# Functional_Schematic.net
KiCad netlist of a schematic drawn in EAGLE
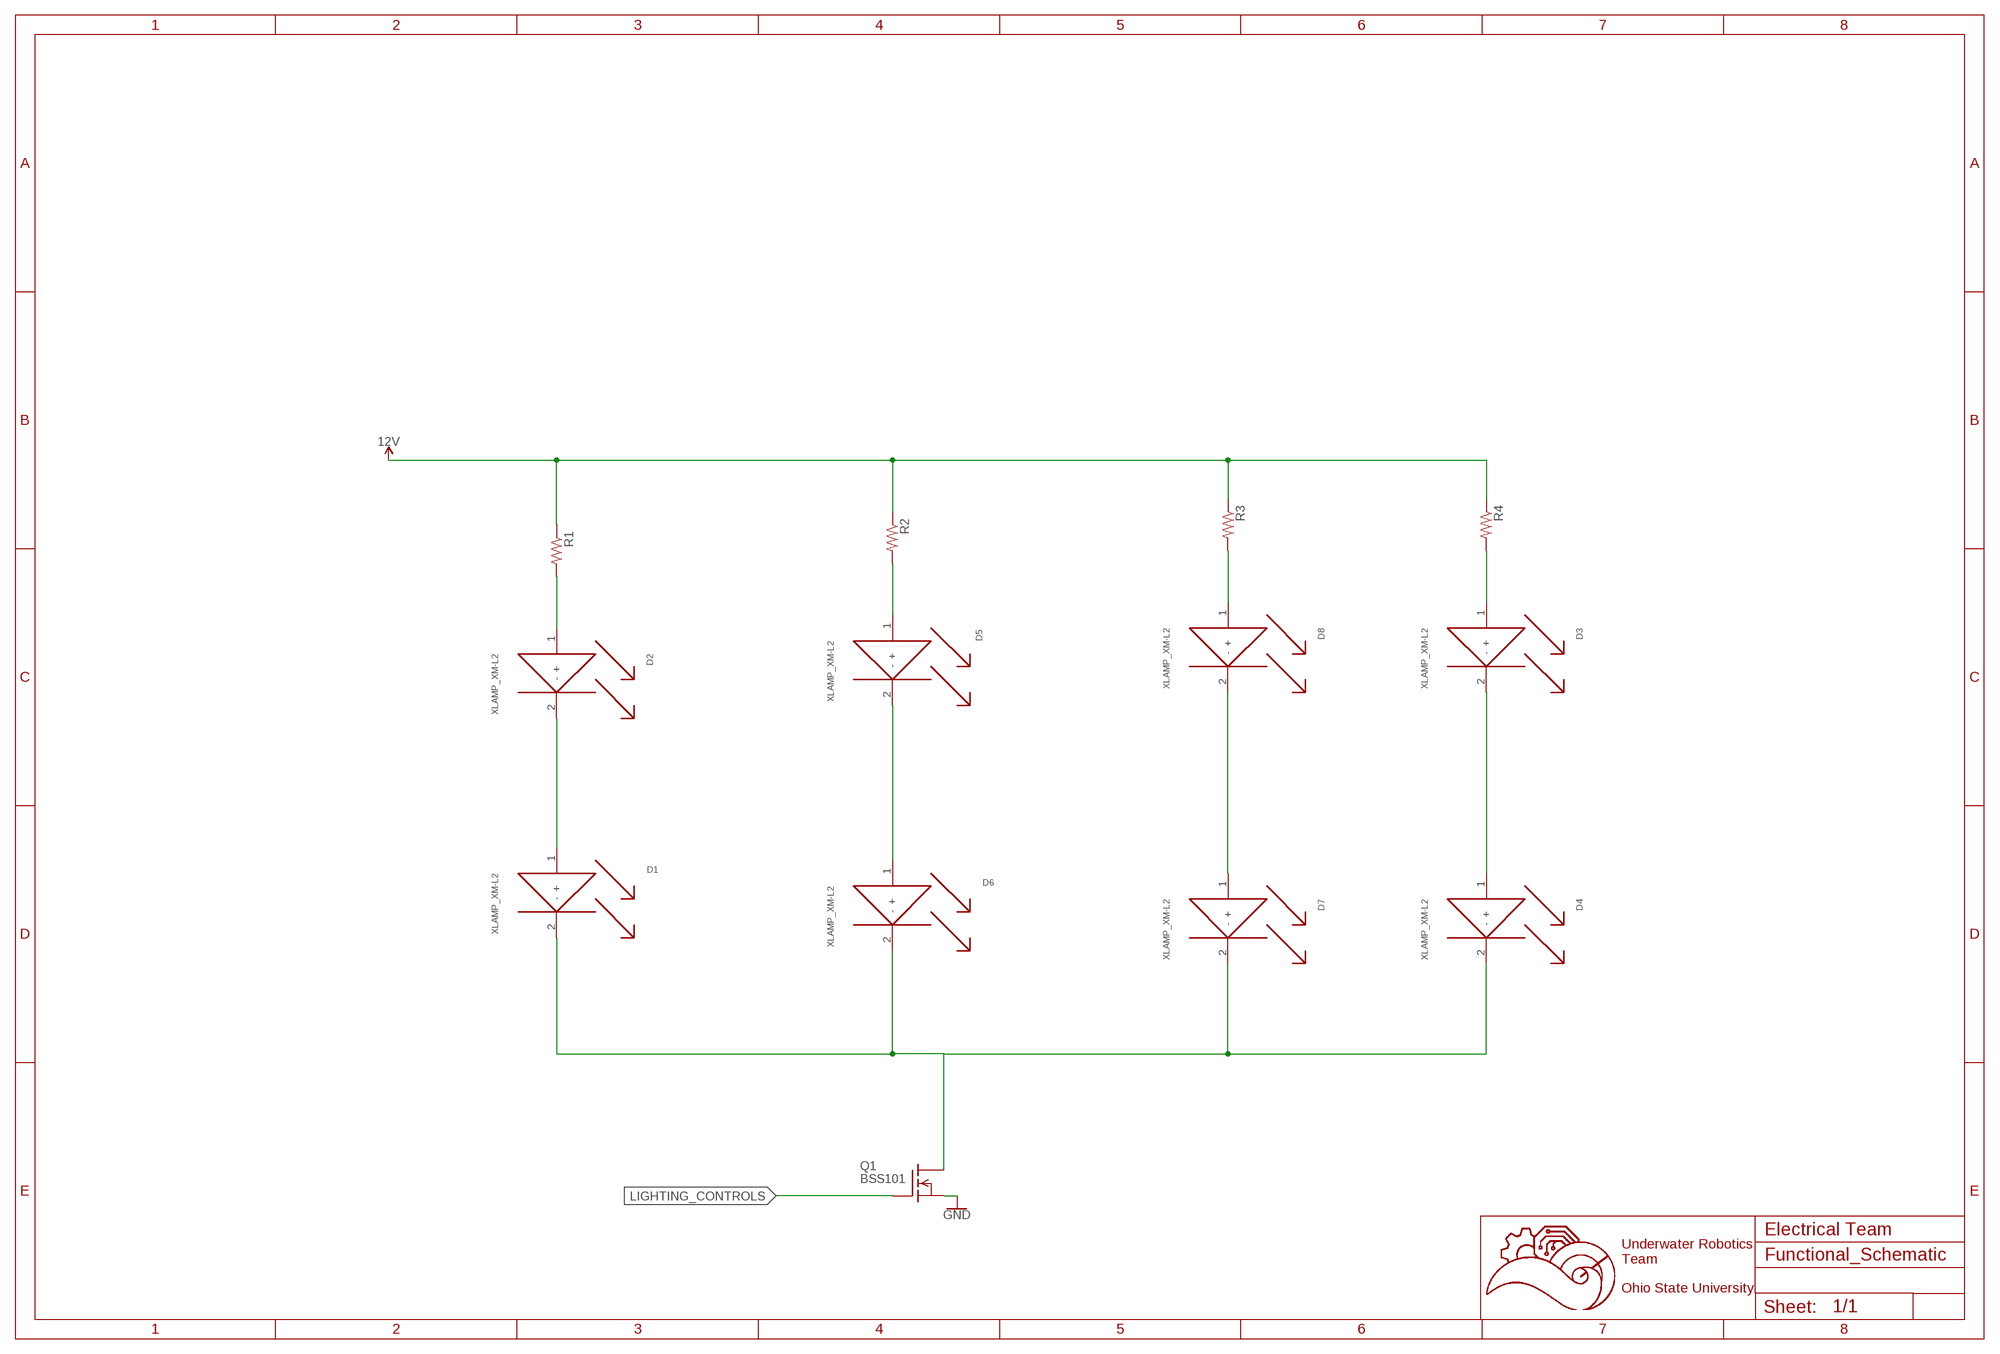
[diagram p0: schematic, sheet 1]

(export (version "E")
  (design (tool "Eeschema 10.0.6"))
  (components
    (comp (ref "D1")
      (value "XLAMP_XM-L2")
      (footprint "eagle-import:XLAMP_XM-L2")
      (libsource (lib "eagle-import") (part "XLAMP_XM-L2"))
    )
    (comp (ref "D2")
      (value "XLAMP_XM-L2")
      (footprint "eagle-import:XLAMP_XM-L2")
      (libsource (lib "eagle-import") (part "XLAMP_XM-L2"))
    )
    (comp (ref "D3")
      (value "XLAMP_XM-L2")
      (footprint "eagle-import:XLAMP_XM-L2")
      (libsource (lib "eagle-import") (part "XLAMP_XM-L2"))
    )
    (comp (ref "D4")
      (value "XLAMP_XM-L2")
      (footprint "eagle-import:XLAMP_XM-L2")
      (libsource (lib "eagle-import") (part "XLAMP_XM-L2"))
    )
    (comp (ref "D5")
      (value "XLAMP_XM-L2")
      (footprint "eagle-import:XLAMP_XM-L2")
      (libsource (lib "eagle-import") (part "XLAMP_XM-L2"))
    )
    (comp (ref "D6")
      (value "XLAMP_XM-L2")
      (footprint "eagle-import:XLAMP_XM-L2")
      (libsource (lib "eagle-import") (part "XLAMP_XM-L2"))
    )
    (comp (ref "D7")
      (value "XLAMP_XM-L2")
      (footprint "eagle-import:XLAMP_XM-L2")
      (libsource (lib "eagle-import") (part "XLAMP_XM-L2"))
    )
    (comp (ref "D8")
      (value "XLAMP_XM-L2")
      (footprint "eagle-import:XLAMP_XM-L2")
      (libsource (lib "eagle-import") (part "XLAMP_XM-L2"))
    )
    (comp (ref "Q1")
      (value "BSS101")
      (footprint "eagle-import:TO92")
      (libsource (lib "eagle-import") (part "BSS101"))
    )
    (comp (ref "R1")
      (value "R-US_R0603")
      (footprint "eagle-import:R0603")
      (libsource (lib "eagle-import") (part "R-US_R0603"))
    )
    (comp (ref "R2")
      (value "R-US_R0603")
      (footprint "eagle-import:R0603")
      (libsource (lib "eagle-import") (part "R-US_R0603"))
    )
    (comp (ref "R3")
      (value "R-US_R0603")
      (footprint "eagle-import:R0603")
      (libsource (lib "eagle-import") (part "R-US_R0603"))
    )
    (comp (ref "R4")
      (value "R-US_R0603")
      (footprint "eagle-import:R0603")
      (libsource (lib "eagle-import") (part "R-US_R0603"))
    )
  )
  (nets
    (net (code "1") (name "12V") (class "Default")
      (node (ref "R1") (pin "1") (pinfunction "1_1") (pintype "passive"))
      (node (ref "R2") (pin "1") (pinfunction "1_1") (pintype "passive"))
      (node (ref "R3") (pin "1") (pinfunction "1_1") (pintype "passive"))
      (node (ref "R4") (pin "1") (pinfunction "1_1") (pintype "passive"))
    )
    (net (code "2") (name "GND") (class "Default")
      (node (ref "Q1") (pin "1") (pinfunction "S_1") (pintype "passive"))
    )
    (net (code "3") (name "LIGHTING_CONTROLS") (class "Default")
      (node (ref "Q1") (pin "2") (pinfunction "G_2") (pintype "passive"))
    )
    (net (code "4") (name "Net-(D1-+)") (class "Default")
      (node (ref "D1") (pin "1") (pinfunction "+_1") (pintype "bidirectional"))
      (node (ref "D2") (pin "2") (pinfunction "-_2") (pintype "bidirectional"))
    )
    (net (code "5") (name "Net-(D1--)") (class "Default")
      (node (ref "D1") (pin "2") (pinfunction "-_2") (pintype "bidirectional"))
      (node (ref "D4") (pin "2") (pinfunction "-_2") (pintype "bidirectional"))
      (node (ref "D6") (pin "2") (pinfunction "-_2") (pintype "bidirectional"))
      (node (ref "D7") (pin "2") (pinfunction "-_2") (pintype "bidirectional"))
      (node (ref "Q1") (pin "3") (pinfunction "D_3") (pintype "passive"))
    )
    (net (code "6") (name "Net-(D2-+)") (class "Default")
      (node (ref "D2") (pin "1") (pinfunction "+_1") (pintype "bidirectional"))
      (node (ref "R1") (pin "2") (pinfunction "2_2") (pintype "passive"))
    )
    (net (code "7") (name "Net-(D3-+)") (class "Default")
      (node (ref "D3") (pin "1") (pinfunction "+_1") (pintype "bidirectional"))
      (node (ref "R4") (pin "2") (pinfunction "2_2") (pintype "passive"))
    )
    (net (code "8") (name "Net-(D3--)") (class "Default")
      (node (ref "D3") (pin "2") (pinfunction "-_2") (pintype "bidirectional"))
      (node (ref "D4") (pin "1") (pinfunction "+_1") (pintype "bidirectional"))
    )
    (net (code "9") (name "Net-(D5-+)") (class "Default")
      (node (ref "D5") (pin "1") (pinfunction "+_1") (pintype "bidirectional"))
      (node (ref "R2") (pin "2") (pinfunction "2_2") (pintype "passive"))
    )
    (net (code "10") (name "Net-(D5--)") (class "Default")
      (node (ref "D5") (pin "2") (pinfunction "-_2") (pintype "bidirectional"))
      (node (ref "D6") (pin "1") (pinfunction "+_1") (pintype "bidirectional"))
    )
    (net (code "11") (name "Net-(D7-+)") (class "Default")
      (node (ref "D7") (pin "1") (pinfunction "+_1") (pintype "bidirectional"))
      (node (ref "D8") (pin "2") (pinfunction "-_2") (pintype "bidirectional"))
    )
    (net (code "12") (name "Net-(D8-+)") (class "Default")
      (node (ref "D8") (pin "1") (pinfunction "+_1") (pintype "bidirectional"))
      (node (ref "R3") (pin "2") (pinfunction "2_2") (pintype "passive"))
    )
  )
)
